# pinus.net
KiCad netlist of a schematic drawn in Altium Designer
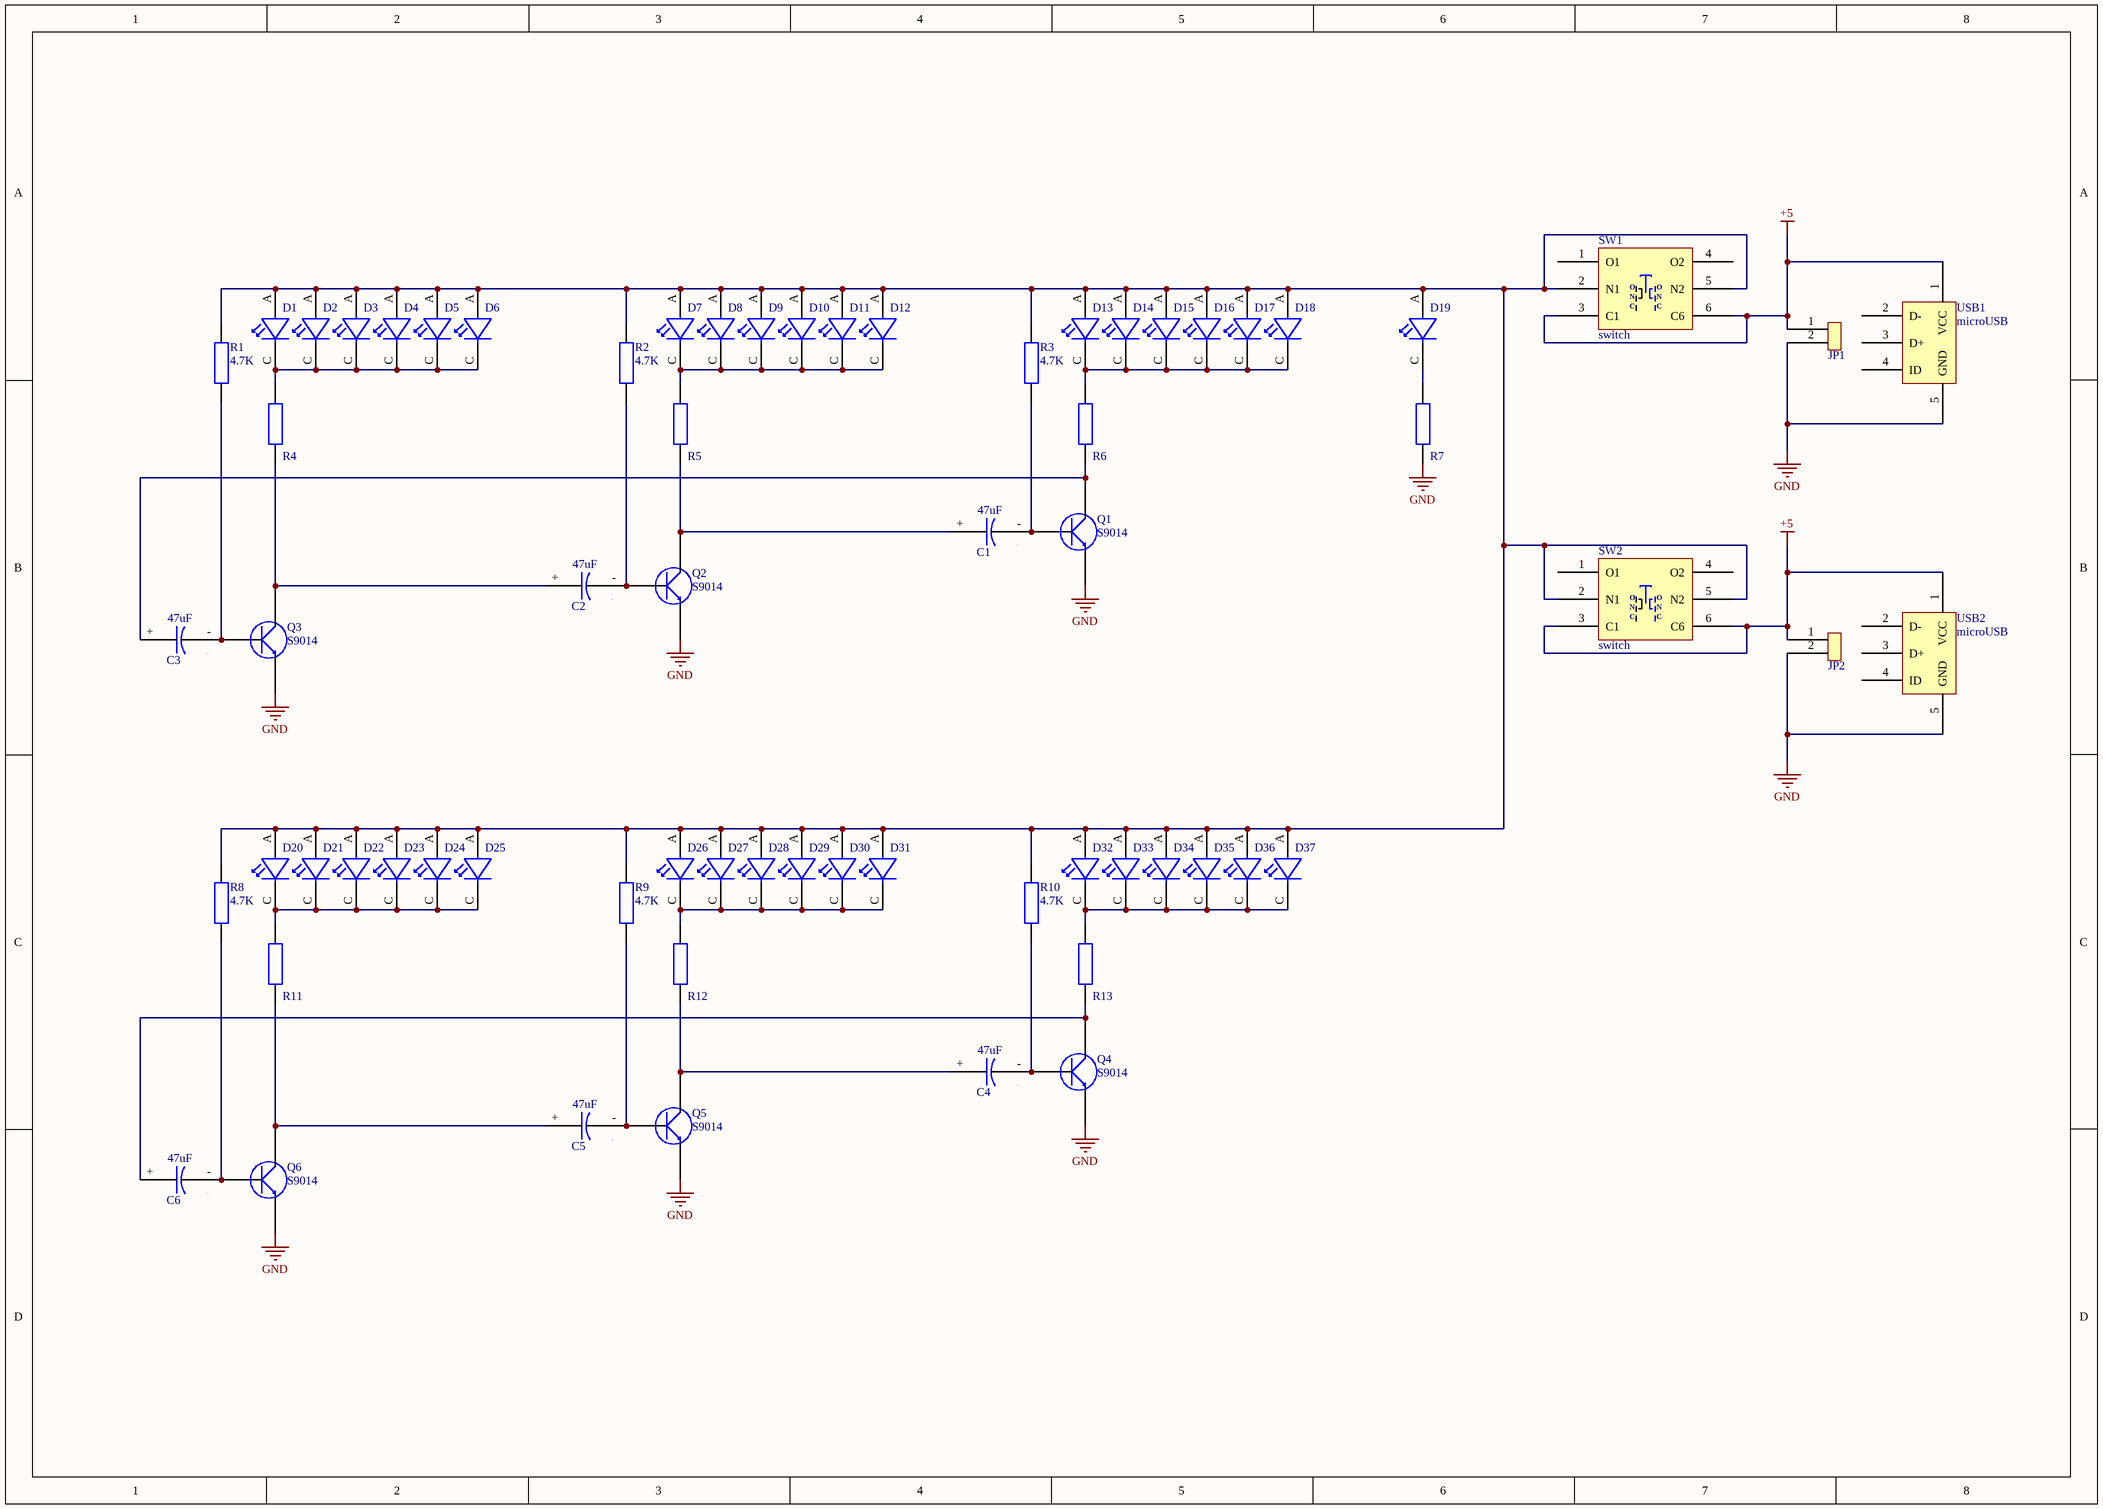
[diagram p0: pinus.SchDoc]

(export (version "E")
  (design (tool "Eeschema 10.0.6"))
  (components
    (comp (ref "C1")
      (value "47uF")
      (footprint "POL_160mil_HORIZONTAL")
      (description "Tụ điện phân cực")
      (libsource (lib "LuongTanDat") (part "Pol-Cap"))
    )
    (comp (ref "C2")
      (value "47uF")
      (footprint "POL_160mil_HORIZONTAL")
      (description "Tụ điện phân cực")
      (libsource (lib "LuongTanDat") (part "Pol-Cap"))
    )
    (comp (ref "C3")
      (value "47uF")
      (footprint "POL_160mil_HORIZONTAL")
      (description "Tụ điện phân cực")
      (libsource (lib "LuongTanDat") (part "Pol-Cap"))
    )
    (comp (ref "C4")
      (value "47uF")
      (footprint "POL_160mil_HORIZONTAL")
      (description "Tụ điện phân cực")
      (libsource (lib "LuongTanDat") (part "Pol-Cap"))
    )
    (comp (ref "C5")
      (value "47uF")
      (footprint "POL_160mil_HORIZONTAL")
      (description "Tụ điện phân cực")
      (libsource (lib "LuongTanDat") (part "Pol-Cap"))
    )
    (comp (ref "C6")
      (value "47uF")
      (footprint "POL_160mil_HORIZONTAL")
      (description "Tụ điện phân cực")
      (libsource (lib "LuongTanDat") (part "Pol-Cap"))
    )
    (comp (ref "D1")
      (value "LED-200mil")
      (footprint "LED-200mil")
      (libsource (lib "LuongTanDat") (part "LED-200mil"))
    )
    (comp (ref "D2")
      (value "LED-200mil")
      (footprint "LED-200mil")
      (libsource (lib "LuongTanDat") (part "LED-200mil"))
    )
    (comp (ref "D3")
      (value "LED-200mil")
      (footprint "LED-200mil")
      (libsource (lib "LuongTanDat") (part "LED-200mil"))
    )
    (comp (ref "D4")
      (value "LED-200mil")
      (footprint "LED-200mil")
      (libsource (lib "LuongTanDat") (part "LED-200mil"))
    )
    (comp (ref "D5")
      (value "LED-200mil")
      (footprint "LED-200mil")
      (libsource (lib "LuongTanDat") (part "LED-200mil"))
    )
    (comp (ref "D6")
      (value "LED-200mil")
      (footprint "LED-200mil")
      (libsource (lib "LuongTanDat") (part "LED-200mil"))
    )
    (comp (ref "D7")
      (value "LED-200mil")
      (footprint "LED-200mil")
      (libsource (lib "LuongTanDat") (part "LED-200mil"))
    )
    (comp (ref "D8")
      (value "LED-200mil")
      (footprint "LED-200mil")
      (libsource (lib "LuongTanDat") (part "LED-200mil"))
    )
    (comp (ref "D9")
      (value "LED-200mil")
      (footprint "LED-200mil")
      (libsource (lib "LuongTanDat") (part "LED-200mil"))
    )
    (comp (ref "D10")
      (value "LED-200mil")
      (footprint "LED-200mil")
      (libsource (lib "LuongTanDat") (part "LED-200mil"))
    )
    (comp (ref "D11")
      (value "LED-200mil")
      (footprint "LED-200mil")
      (libsource (lib "LuongTanDat") (part "LED-200mil"))
    )
    (comp (ref "D12")
      (value "LED-200mil")
      (footprint "LED-200mil")
      (libsource (lib "LuongTanDat") (part "LED-200mil"))
    )
    (comp (ref "D13")
      (value "LED-200mil")
      (footprint "LED-200mil")
      (libsource (lib "LuongTanDat") (part "LED-200mil"))
    )
    (comp (ref "D14")
      (value "LED-200mil")
      (footprint "LED-200mil")
      (libsource (lib "LuongTanDat") (part "LED-200mil"))
    )
    (comp (ref "D15")
      (value "LED-200mil")
      (footprint "LED-200mil")
      (libsource (lib "LuongTanDat") (part "LED-200mil"))
    )
    (comp (ref "D16")
      (value "LED-200mil")
      (footprint "LED-200mil")
      (libsource (lib "LuongTanDat") (part "LED-200mil"))
    )
    (comp (ref "D17")
      (value "LED-200mil")
      (footprint "LED-200mil")
      (libsource (lib "LuongTanDat") (part "LED-200mil"))
    )
    (comp (ref "D18")
      (value "LED-200mil")
      (footprint "LED-200mil")
      (libsource (lib "LuongTanDat") (part "LED-200mil"))
    )
    (comp (ref "D19")
      (value "LED-200mil")
      (footprint "LED-200mil")
      (libsource (lib "LuongTanDat") (part "LED-200mil"))
    )
    (comp (ref "D20")
      (value "LED-200mil")
      (footprint "LED-200mil")
      (libsource (lib "LuongTanDat") (part "LED-200mil"))
    )
    (comp (ref "D21")
      (value "LED-200mil")
      (footprint "LED-200mil")
      (libsource (lib "LuongTanDat") (part "LED-200mil"))
    )
    (comp (ref "D22")
      (value "LED-200mil")
      (footprint "LED-200mil")
      (libsource (lib "LuongTanDat") (part "LED-200mil"))
    )
    (comp (ref "D23")
      (value "LED-200mil")
      (footprint "LED-200mil")
      (libsource (lib "LuongTanDat") (part "LED-200mil"))
    )
    (comp (ref "D24")
      (value "LED-200mil")
      (footprint "LED-200mil")
      (libsource (lib "LuongTanDat") (part "LED-200mil"))
    )
    (comp (ref "D25")
      (value "LED-200mil")
      (footprint "LED-200mil")
      (libsource (lib "LuongTanDat") (part "LED-200mil"))
    )
    (comp (ref "D26")
      (value "LED-200mil")
      (footprint "LED-200mil")
      (libsource (lib "LuongTanDat") (part "LED-200mil"))
    )
    (comp (ref "D27")
      (value "LED-200mil")
      (footprint "LED-200mil")
      (libsource (lib "LuongTanDat") (part "LED-200mil"))
    )
    (comp (ref "D28")
      (value "LED-200mil")
      (footprint "LED-200mil")
      (libsource (lib "LuongTanDat") (part "LED-200mil"))
    )
    (comp (ref "D29")
      (value "LED-200mil")
      (footprint "LED-200mil")
      (libsource (lib "LuongTanDat") (part "LED-200mil"))
    )
    (comp (ref "D30")
      (value "LED-200mil")
      (footprint "LED-200mil")
      (libsource (lib "LuongTanDat") (part "LED-200mil"))
    )
    (comp (ref "D31")
      (value "LED-200mil")
      (footprint "LED-200mil")
      (libsource (lib "LuongTanDat") (part "LED-200mil"))
    )
    (comp (ref "D32")
      (value "LED-200mil")
      (footprint "LED-200mil")
      (libsource (lib "LuongTanDat") (part "LED-200mil"))
    )
    (comp (ref "D33")
      (value "LED-200mil")
      (footprint "LED-200mil")
      (libsource (lib "LuongTanDat") (part "LED-200mil"))
    )
    (comp (ref "D34")
      (value "LED-200mil")
      (footprint "LED-200mil")
      (libsource (lib "LuongTanDat") (part "LED-200mil"))
    )
    (comp (ref "D35")
      (value "LED-200mil")
      (footprint "LED-200mil")
      (libsource (lib "LuongTanDat") (part "LED-200mil"))
    )
    (comp (ref "D36")
      (value "LED-200mil")
      (footprint "LED-200mil")
      (libsource (lib "LuongTanDat") (part "LED-200mil"))
    )
    (comp (ref "D37")
      (value "LED-200mil")
      (footprint "LED-200mil")
      (libsource (lib "LuongTanDat") (part "LED-200mil"))
    )
    (comp (ref "JP1") (value "JP_2") (footprint "JP_2") (libsource (lib "LuongTanDat") (part "JP_2")))
    (comp (ref "JP2") (value "JP_2") (footprint "JP_2") (libsource (lib "LuongTanDat") (part "JP_2")))
    (comp (ref "Q1") (value "S9014") (footprint "S9014") (libsource (lib "LuongTanDat") (part "S9014")))
    (comp (ref "Q2") (value "S9014") (footprint "S9014") (libsource (lib "LuongTanDat") (part "S9014")))
    (comp (ref "Q3") (value "S9014") (footprint "S9014") (libsource (lib "LuongTanDat") (part "S9014")))
    (comp (ref "Q4") (value "S9014") (footprint "S9014") (libsource (lib "LuongTanDat") (part "S9014")))
    (comp (ref "Q5") (value "S9014") (footprint "S9014") (libsource (lib "LuongTanDat") (part "S9014")))
    (comp (ref "Q6") (value "S9014") (footprint "S9014") (libsource (lib "LuongTanDat") (part "S9014")))
    (comp (ref "R1")
      (value "4.7K")
      (footprint "RES")
      (description "điện trở size nhỏ")
      (libsource (lib "LuongTanDat") (part "RES"))
    )
    (comp (ref "R2")
      (value "4.7K")
      (footprint "RES")
      (description "điện trở size nhỏ")
      (libsource (lib "LuongTanDat") (part "RES"))
    )
    (comp (ref "R3")
      (value "4.7K")
      (footprint "RES")
      (description "điện trở size nhỏ")
      (libsource (lib "LuongTanDat") (part "RES"))
    )
    (comp (ref "R4")
      (value "100R")
      (footprint "RES")
      (description "điện trở size nhỏ")
      (libsource (lib "LuongTanDat") (part "RES"))
    )
    (comp (ref "R5")
      (value "100R")
      (footprint "RES")
      (description "điện trở size nhỏ")
      (libsource (lib "LuongTanDat") (part "RES"))
    )
    (comp (ref "R6")
      (value "100R")
      (footprint "RES")
      (description "điện trở size nhỏ")
      (libsource (lib "LuongTanDat") (part "RES"))
    )
    (comp (ref "R7")
      (value "100R")
      (footprint "RES")
      (description "điện trở size nhỏ")
      (libsource (lib "LuongTanDat") (part "RES"))
    )
    (comp (ref "R8")
      (value "4.7K")
      (footprint "RES")
      (description "điện trở size nhỏ")
      (libsource (lib "LuongTanDat") (part "RES"))
    )
    (comp (ref "R9")
      (value "4.7K")
      (footprint "RES")
      (description "điện trở size nhỏ")
      (libsource (lib "LuongTanDat") (part "RES"))
    )
    (comp (ref "R10")
      (value "4.7K")
      (footprint "RES")
      (description "điện trở size nhỏ")
      (libsource (lib "LuongTanDat") (part "RES"))
    )
    (comp (ref "R11")
      (value "100R")
      (footprint "RES")
      (description "điện trở size nhỏ")
      (libsource (lib "LuongTanDat") (part "RES"))
    )
    (comp (ref "R12")
      (value "100R")
      (footprint "RES")
      (description "điện trở size nhỏ")
      (libsource (lib "LuongTanDat") (part "RES"))
    )
    (comp (ref "R13")
      (value "100R")
      (footprint "RES")
      (description "điện trở size nhỏ")
      (libsource (lib "LuongTanDat") (part "RES"))
    )
    (comp (ref "SW1") (value "switch") (footprint "switch") (libsource (lib "LuongTanDat") (part "switch")))
    (comp (ref "SW2") (value "switch") (footprint "switch") (libsource (lib "LuongTanDat") (part "switch")))
    (comp (ref "USB1")
      (value "microUSB")
      (footprint "MicroUSB_F_2")
      (libsource (lib "LuongTanDat") (part "microUSB"))
    )
    (comp (ref "USB2")
      (value "microUSB")
      (footprint "MicroUSB_F_2")
      (libsource (lib "LuongTanDat") (part "microUSB"))
    )
  )
  (nets
    (net (code "1") (name "+5") (class "Default")
      (node (ref "JP1") (pin "1") (pinfunction "1_1") (pintype "passive"))
      (node (ref "JP2") (pin "1") (pinfunction "1_1") (pintype "passive"))
      (node (ref "SW1") (pin "3") (pinfunction "C1_3") (pintype "passive"))
      (node (ref "SW1") (pin "6") (pinfunction "C6_6") (pintype "passive"))
      (node (ref "SW2") (pin "3") (pinfunction "C1_3") (pintype "passive"))
      (node (ref "SW2") (pin "6") (pinfunction "C6_6") (pintype "passive"))
      (node (ref "USB1") (pin "1") (pinfunction "VCC_1") (pintype "passive"))
      (node (ref "USB2") (pin "1") (pinfunction "VCC_1") (pintype "passive"))
    )
    (net (code "2") (name "GND") (class "Default")
      (node (ref "JP1") (pin "2") (pinfunction "2_2") (pintype "passive"))
      (node (ref "JP2") (pin "2") (pinfunction "2_2") (pintype "passive"))
      (node (ref "Q1") (pin "1") (pinfunction "1_1") (pintype "passive"))
      (node (ref "Q2") (pin "1") (pinfunction "1_1") (pintype "passive"))
      (node (ref "Q3") (pin "1") (pinfunction "1_1") (pintype "passive"))
      (node (ref "Q4") (pin "1") (pinfunction "1_1") (pintype "passive"))
      (node (ref "Q5") (pin "1") (pinfunction "1_1") (pintype "passive"))
      (node (ref "Q6") (pin "1") (pinfunction "1_1") (pintype "passive"))
      (node (ref "R7") (pin "1") (pinfunction "1_1") (pintype "passive"))
      (node (ref "USB1") (pin "5") (pinfunction "GND_5") (pintype "passive"))
      (node (ref "USB2") (pin "5") (pinfunction "GND_5") (pintype "passive"))
    )
    (net (code "3") (name "Net-(C1-Pad+)") (class "Default")
      (node (ref "C1") (pin "+") (pintype "passive"))
      (node (ref "Q2") (pin "3") (pinfunction "3_3") (pintype "passive"))
      (node (ref "R5") (pin "1") (pinfunction "1_1") (pintype "passive"))
    )
    (net (code "4") (name "Net-(C1-Pad-)") (class "Default")
      (node (ref "C1") (pin "-") (pintype "passive"))
      (node (ref "Q1") (pin "2") (pinfunction "2_2") (pintype "passive"))
      (node (ref "R3") (pin "1") (pinfunction "1_1") (pintype "passive"))
    )
    (net (code "5") (name "Net-(C2-Pad+)") (class "Default")
      (node (ref "C2") (pin "+") (pintype "passive"))
      (node (ref "Q3") (pin "3") (pinfunction "3_3") (pintype "passive"))
      (node (ref "R4") (pin "1") (pinfunction "1_1") (pintype "passive"))
    )
    (net (code "6") (name "Net-(C2-Pad-)") (class "Default")
      (node (ref "C2") (pin "-") (pintype "passive"))
      (node (ref "Q2") (pin "2") (pinfunction "2_2") (pintype "passive"))
      (node (ref "R2") (pin "1") (pinfunction "1_1") (pintype "passive"))
    )
    (net (code "7") (name "Net-(C3-Pad+)") (class "Default")
      (node (ref "C3") (pin "+") (pintype "passive"))
      (node (ref "Q1") (pin "3") (pinfunction "3_3") (pintype "passive"))
      (node (ref "R6") (pin "1") (pinfunction "1_1") (pintype "passive"))
    )
    (net (code "8") (name "Net-(C3-Pad-)") (class "Default")
      (node (ref "C3") (pin "-") (pintype "passive"))
      (node (ref "Q3") (pin "2") (pinfunction "2_2") (pintype "passive"))
      (node (ref "R1") (pin "1") (pinfunction "1_1") (pintype "passive"))
    )
    (net (code "9") (name "Net-(C4-Pad+)") (class "Default")
      (node (ref "C4") (pin "+") (pintype "passive"))
      (node (ref "Q5") (pin "3") (pinfunction "3_3") (pintype "passive"))
      (node (ref "R12") (pin "1") (pinfunction "1_1") (pintype "passive"))
    )
    (net (code "10") (name "Net-(C4-Pad-)") (class "Default")
      (node (ref "C4") (pin "-") (pintype "passive"))
      (node (ref "Q4") (pin "2") (pinfunction "2_2") (pintype "passive"))
      (node (ref "R10") (pin "1") (pinfunction "1_1") (pintype "passive"))
    )
    (net (code "11") (name "Net-(C5-Pad+)") (class "Default")
      (node (ref "C5") (pin "+") (pintype "passive"))
      (node (ref "Q6") (pin "3") (pinfunction "3_3") (pintype "passive"))
      (node (ref "R11") (pin "1") (pinfunction "1_1") (pintype "passive"))
    )
    (net (code "12") (name "Net-(C5-Pad-)") (class "Default")
      (node (ref "C5") (pin "-") (pintype "passive"))
      (node (ref "Q5") (pin "2") (pinfunction "2_2") (pintype "passive"))
      (node (ref "R9") (pin "1") (pinfunction "1_1") (pintype "passive"))
    )
    (net (code "13") (name "Net-(C6-Pad+)") (class "Default")
      (node (ref "C6") (pin "+") (pintype "passive"))
      (node (ref "Q4") (pin "3") (pinfunction "3_3") (pintype "passive"))
      (node (ref "R13") (pin "1") (pinfunction "1_1") (pintype "passive"))
    )
    (net (code "14") (name "Net-(C6-Pad-)") (class "Default")
      (node (ref "C6") (pin "-") (pintype "passive"))
      (node (ref "Q6") (pin "2") (pinfunction "2_2") (pintype "passive"))
      (node (ref "R8") (pin "1") (pinfunction "1_1") (pintype "passive"))
    )
    (net (code "15") (name "Net-(D1-1)") (class "Default")
      (node (ref "D1") (pin "A") (pinfunction "1_A") (pintype "passive"))
      (node (ref "D10") (pin "A") (pinfunction "1_A") (pintype "passive"))
      (node (ref "D11") (pin "A") (pinfunction "1_A") (pintype "passive"))
      (node (ref "D12") (pin "A") (pinfunction "1_A") (pintype "passive"))
      (node (ref "D13") (pin "A") (pinfunction "1_A") (pintype "passive"))
      (node (ref "D14") (pin "A") (pinfunction "1_A") (pintype "passive"))
      (node (ref "D15") (pin "A") (pinfunction "1_A") (pintype "passive"))
      (node (ref "D16") (pin "A") (pinfunction "1_A") (pintype "passive"))
      (node (ref "D17") (pin "A") (pinfunction "1_A") (pintype "passive"))
      (node (ref "D18") (pin "A") (pinfunction "1_A") (pintype "passive"))
      (node (ref "D19") (pin "A") (pinfunction "1_A") (pintype "passive"))
      (node (ref "D2") (pin "A") (pinfunction "1_A") (pintype "passive"))
      (node (ref "D20") (pin "A") (pinfunction "1_A") (pintype "passive"))
      (node (ref "D21") (pin "A") (pinfunction "1_A") (pintype "passive"))
      (node (ref "D22") (pin "A") (pinfunction "1_A") (pintype "passive"))
      (node (ref "D23") (pin "A") (pinfunction "1_A") (pintype "passive"))
      (node (ref "D24") (pin "A") (pinfunction "1_A") (pintype "passive"))
      (node (ref "D25") (pin "A") (pinfunction "1_A") (pintype "passive"))
      (node (ref "D26") (pin "A") (pinfunction "1_A") (pintype "passive"))
      (node (ref "D27") (pin "A") (pinfunction "1_A") (pintype "passive"))
      (node (ref "D28") (pin "A") (pinfunction "1_A") (pintype "passive"))
      (node (ref "D29") (pin "A") (pinfunction "1_A") (pintype "passive"))
      (node (ref "D3") (pin "A") (pinfunction "1_A") (pintype "passive"))
      (node (ref "D30") (pin "A") (pinfunction "1_A") (pintype "passive"))
      (node (ref "D31") (pin "A") (pinfunction "1_A") (pintype "passive"))
      (node (ref "D32") (pin "A") (pinfunction "1_A") (pintype "passive"))
      (node (ref "D33") (pin "A") (pinfunction "1_A") (pintype "passive"))
      (node (ref "D34") (pin "A") (pinfunction "1_A") (pintype "passive"))
      (node (ref "D35") (pin "A") (pinfunction "1_A") (pintype "passive"))
      (node (ref "D36") (pin "A") (pinfunction "1_A") (pintype "passive"))
      (node (ref "D37") (pin "A") (pinfunction "1_A") (pintype "passive"))
      (node (ref "D4") (pin "A") (pinfunction "1_A") (pintype "passive"))
      (node (ref "D5") (pin "A") (pinfunction "1_A") (pintype "passive"))
      (node (ref "D6") (pin "A") (pinfunction "1_A") (pintype "passive"))
      (node (ref "D7") (pin "A") (pinfunction "1_A") (pintype "passive"))
      (node (ref "D8") (pin "A") (pinfunction "1_A") (pintype "passive"))
      (node (ref "D9") (pin "A") (pinfunction "1_A") (pintype "passive"))
      (node (ref "R1") (pin "2") (pinfunction "2_2") (pintype "passive"))
      (node (ref "R10") (pin "2") (pinfunction "2_2") (pintype "passive"))
      (node (ref "R2") (pin "2") (pinfunction "2_2") (pintype "passive"))
      (node (ref "R3") (pin "2") (pinfunction "2_2") (pintype "passive"))
      (node (ref "R8") (pin "2") (pinfunction "2_2") (pintype "passive"))
      (node (ref "R9") (pin "2") (pinfunction "2_2") (pintype "passive"))
      (node (ref "SW1") (pin "2") (pinfunction "N1_2") (pintype "passive"))
      (node (ref "SW1") (pin "5") (pinfunction "N2_5") (pintype "passive"))
      (node (ref "SW2") (pin "2") (pinfunction "N1_2") (pintype "passive"))
      (node (ref "SW2") (pin "5") (pinfunction "N2_5") (pintype "passive"))
    )
    (net (code "16") (name "Net-(D1-2)") (class "Default")
      (node (ref "D1") (pin "C") (pinfunction "2_C") (pintype "passive"))
      (node (ref "D2") (pin "C") (pinfunction "2_C") (pintype "passive"))
      (node (ref "D3") (pin "C") (pinfunction "2_C") (pintype "passive"))
      (node (ref "D4") (pin "C") (pinfunction "2_C") (pintype "passive"))
      (node (ref "D5") (pin "C") (pinfunction "2_C") (pintype "passive"))
      (node (ref "D6") (pin "C") (pinfunction "2_C") (pintype "passive"))
      (node (ref "R4") (pin "2") (pinfunction "2_2") (pintype "passive"))
    )
    (net (code "17") (name "Net-(D10-2)") (class "Default")
      (node (ref "D10") (pin "C") (pinfunction "2_C") (pintype "passive"))
      (node (ref "D11") (pin "C") (pinfunction "2_C") (pintype "passive"))
      (node (ref "D12") (pin "C") (pinfunction "2_C") (pintype "passive"))
      (node (ref "D7") (pin "C") (pinfunction "2_C") (pintype "passive"))
      (node (ref "D8") (pin "C") (pinfunction "2_C") (pintype "passive"))
      (node (ref "D9") (pin "C") (pinfunction "2_C") (pintype "passive"))
      (node (ref "R5") (pin "2") (pinfunction "2_2") (pintype "passive"))
    )
    (net (code "18") (name "Net-(D13-2)") (class "Default")
      (node (ref "D13") (pin "C") (pinfunction "2_C") (pintype "passive"))
      (node (ref "D14") (pin "C") (pinfunction "2_C") (pintype "passive"))
      (node (ref "D15") (pin "C") (pinfunction "2_C") (pintype "passive"))
      (node (ref "D16") (pin "C") (pinfunction "2_C") (pintype "passive"))
      (node (ref "D17") (pin "C") (pinfunction "2_C") (pintype "passive"))
      (node (ref "D18") (pin "C") (pinfunction "2_C") (pintype "passive"))
      (node (ref "R6") (pin "2") (pinfunction "2_2") (pintype "passive"))
    )
    (net (code "19") (name "Net-(D19-2)") (class "Default")
      (node (ref "D19") (pin "C") (pinfunction "2_C") (pintype "passive"))
      (node (ref "R7") (pin "2") (pinfunction "2_2") (pintype "passive"))
    )
    (net (code "20") (name "Net-(D20-2)") (class "Default")
      (node (ref "D20") (pin "C") (pinfunction "2_C") (pintype "passive"))
      (node (ref "D21") (pin "C") (pinfunction "2_C") (pintype "passive"))
      (node (ref "D22") (pin "C") (pinfunction "2_C") (pintype "passive"))
      (node (ref "D23") (pin "C") (pinfunction "2_C") (pintype "passive"))
      (node (ref "D24") (pin "C") (pinfunction "2_C") (pintype "passive"))
      (node (ref "D25") (pin "C") (pinfunction "2_C") (pintype "passive"))
      (node (ref "R11") (pin "2") (pinfunction "2_2") (pintype "passive"))
    )
    (net (code "21") (name "Net-(D26-2)") (class "Default")
      (node (ref "D26") (pin "C") (pinfunction "2_C") (pintype "passive"))
      (node (ref "D27") (pin "C") (pinfunction "2_C") (pintype "passive"))
      (node (ref "D28") (pin "C") (pinfunction "2_C") (pintype "passive"))
      (node (ref "D29") (pin "C") (pinfunction "2_C") (pintype "passive"))
      (node (ref "D30") (pin "C") (pinfunction "2_C") (pintype "passive"))
      (node (ref "D31") (pin "C") (pinfunction "2_C") (pintype "passive"))
      (node (ref "R12") (pin "2") (pinfunction "2_2") (pintype "passive"))
    )
    (net (code "22") (name "Net-(D32-2)") (class "Default")
      (node (ref "D32") (pin "C") (pinfunction "2_C") (pintype "passive"))
      (node (ref "D33") (pin "C") (pinfunction "2_C") (pintype "passive"))
      (node (ref "D34") (pin "C") (pinfunction "2_C") (pintype "passive"))
      (node (ref "D35") (pin "C") (pinfunction "2_C") (pintype "passive"))
      (node (ref "D36") (pin "C") (pinfunction "2_C") (pintype "passive"))
      (node (ref "D37") (pin "C") (pinfunction "2_C") (pintype "passive"))
      (node (ref "R13") (pin "2") (pinfunction "2_2") (pintype "passive"))
    )
    (net (code "23") (name "unconnected-(SW1-O1-Pad1)") (class "Default")
      (node (ref "SW1") (pin "1") (pinfunction "O1_1") (pintype "passive"))
    )
    (net (code "24") (name "unconnected-(SW1-O2-Pad4)") (class "Default")
      (node (ref "SW1") (pin "4") (pinfunction "O2_4") (pintype "passive"))
    )
    (net (code "25") (name "unconnected-(SW2-O1-Pad1)") (class "Default")
      (node (ref "SW2") (pin "1") (pinfunction "O1_1") (pintype "passive"))
    )
    (net (code "26") (name "unconnected-(SW2-O2-Pad4)") (class "Default")
      (node (ref "SW2") (pin "4") (pinfunction "O2_4") (pintype "passive"))
    )
    (net (code "27") (name "unconnected-(USB1-D+-Pad3)") (class "Default")
      (node (ref "USB1") (pin "3") (pinfunction "D+_3") (pintype "passive"))
    )
    (net (code "28") (name "unconnected-(USB1-D--Pad2)") (class "Default")
      (node (ref "USB1") (pin "2") (pinfunction "D-_2") (pintype "passive"))
    )
    (net (code "29") (name "unconnected-(USB1-ID-Pad4)") (class "Default")
      (node (ref "USB1") (pin "4") (pinfunction "ID_4") (pintype "passive"))
    )
    (net (code "30") (name "unconnected-(USB2-D+-Pad3)") (class "Default")
      (node (ref "USB2") (pin "3") (pinfunction "D+_3") (pintype "passive"))
    )
    (net (code "31") (name "unconnected-(USB2-D--Pad2)") (class "Default")
      (node (ref "USB2") (pin "2") (pinfunction "D-_2") (pintype "passive"))
    )
    (net (code "32") (name "unconnected-(USB2-ID-Pad4)") (class "Default")
      (node (ref "USB2") (pin "4") (pinfunction "ID_4") (pintype "passive"))
    )
  )
)
